# nm_npu_proc.net
KiCad netlist of a schematic drawn in Altium Designer
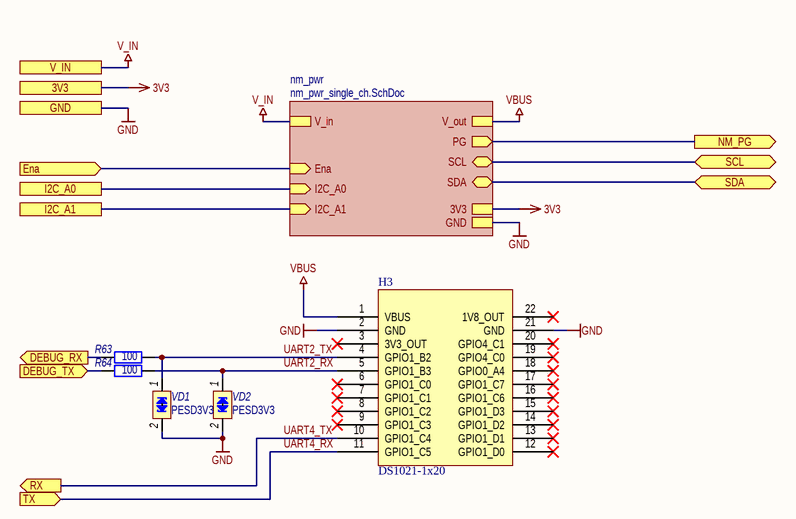
[diagram p0: nm_npu_proc.SchDoc]

(export (version "E")
  (design (tool "Eeschema 10.0.6"))
  (components
    (comp (ref "H3")
      (value "DS1021-1x20")
      (footprint "DS1021-1x20")
      (libsource (lib "DS1021-1x20") (part "DS1021-1x20"))
    )
    (comp (ref "R63")
      (value "100")
      (footprint "SMD_0603")
      (description "Resistor")
      (libsource (lib "Passive") (part "Resistor"))
    )
    (comp (ref "R64")
      (value "100")
      (footprint "SMD_0603")
      (description "Resistor")
      (libsource (lib "Passive") (part "Resistor"))
    )
    (comp (ref "VD1")
      (value "PESD3V3")
      (footprint "SOD-323")
      (description "Low capacitance bidirectional ESD protection diodes")
      (libsource (lib "Diod") (part "PESDxL1BA"))
    )
    (comp (ref "VD2")
      (value "PESD3V3")
      (footprint "SOD-323")
      (description "Low capacitance bidirectional ESD protection diodes")
      (libsource (lib "Diod") (part "PESDxL1BA"))
    )
  )
  (nets
    (net (code "1") (name "/DEBUG_RX") (class "Default")
      (node (ref "R63") (pin "1") (pinfunction "1_1") (pintype "passive"))
    )
    (net (code "2") (name "/DEBUG_TX") (class "Default")
      (node (ref "R64") (pin "1") (pinfunction "1_1") (pintype "passive"))
    )
    (net (code "9") (name "/UART2_RX") (class "Default")
      (node (ref "H3") (pin "5") (pinfunction "GPIO1_B3_5") (pintype "passive"))
      (node (ref "R64") (pin "2") (pinfunction "2_2") (pintype "passive"))
      (node (ref "VD2") (pin "1") (pinfunction "cathode_1_1") (pintype "passive"))
    )
    (net (code "10") (name "/UART2_TX") (class "Default")
      (node (ref "H3") (pin "4") (pinfunction "GPIO1_B2_4") (pintype "passive"))
      (node (ref "R63") (pin "2") (pinfunction "2_2") (pintype "passive"))
      (node (ref "VD1") (pin "1") (pinfunction "cathode_1_1") (pintype "passive"))
    )
    (net (code "11") (name "/UART4_RX") (class "Default")
      (node (ref "H3") (pin "11") (pinfunction "GPIO1_C5_11") (pintype "passive"))
    )
    (net (code "12") (name "/UART4_TX") (class "Default")
      (node (ref "H3") (pin "10") (pinfunction "GPIO1_C4_10") (pintype "passive"))
    )
    (net (code "14") (name "GND") (class "Default")
      (node (ref "H3") (pin "2") (pinfunction "GND_2") (pintype "power_in"))
      (node (ref "H3") (pin "21") (pinfunction "GND_21") (pintype "power_in"))
      (node (ref "VD1") (pin "2") (pinfunction "cathode_2_2") (pintype "passive"))
      (node (ref "VD2") (pin "2") (pinfunction "cathode_2_2") (pintype "passive"))
    )
    (net (code "15") (name "VBUS") (class "Default")
      (node (ref "H3") (pin "1") (pinfunction "VBUS_1") (pintype "power_in"))
    )
    (net (code "17") (name "unconnected-(H3-1V8_OUT-Pad22)") (class "Default")
      (node (ref "H3") (pin "22") (pinfunction "1V8_OUT_22") (pintype "power_in+no_connect"))
    )
    (net (code "18") (name "unconnected-(H3-3V3_OUT-Pad3)") (class "Default")
      (node (ref "H3") (pin "3") (pinfunction "3V3_OUT_3") (pintype "power_in+no_connect"))
    )
    (net (code "19") (name "unconnected-(H3-GPIO0_A4-Pad18)") (class "Default")
      (node (ref "H3") (pin "18") (pinfunction "GPIO0_A4_18") (pintype "passive+no_connect"))
    )
    (net (code "20") (name "unconnected-(H3-GPIO1_C0-Pad6)") (class "Default")
      (node (ref "H3") (pin "6") (pinfunction "GPIO1_C0_6") (pintype "passive+no_connect"))
    )
    (net (code "21") (name "unconnected-(H3-GPIO1_C1-Pad7)") (class "Default")
      (node (ref "H3") (pin "7") (pinfunction "GPIO1_C1_7") (pintype "passive+no_connect"))
    )
    (net (code "22") (name "unconnected-(H3-GPIO1_C2-Pad8)") (class "Default")
      (node (ref "H3") (pin "8") (pinfunction "GPIO1_C2_8") (pintype "passive+no_connect"))
    )
    (net (code "23") (name "unconnected-(H3-GPIO1_C3-Pad9)") (class "Default")
      (node (ref "H3") (pin "9") (pinfunction "GPIO1_C3_9") (pintype "passive+no_connect"))
    )
    (net (code "24") (name "unconnected-(H3-GPIO1_C6-Pad16)") (class "Default")
      (node (ref "H3") (pin "16") (pinfunction "GPIO1_C6_16") (pintype "passive+no_connect"))
    )
    (net (code "25") (name "unconnected-(H3-GPIO1_C7-Pad17)") (class "Default")
      (node (ref "H3") (pin "17") (pinfunction "GPIO1_C7_17") (pintype "passive+no_connect"))
    )
    (net (code "26") (name "unconnected-(H3-GPIO1_D0-Pad12)") (class "Default")
      (node (ref "H3") (pin "12") (pinfunction "GPIO1_D0_12") (pintype "passive+no_connect"))
    )
    (net (code "27") (name "unconnected-(H3-GPIO1_D1-Pad13)") (class "Default")
      (node (ref "H3") (pin "13") (pinfunction "GPIO1_D1_13") (pintype "passive+no_connect"))
    )
    (net (code "28") (name "unconnected-(H3-GPIO1_D2-Pad14)") (class "Default")
      (node (ref "H3") (pin "14") (pinfunction "GPIO1_D2_14") (pintype "passive+no_connect"))
    )
    (net (code "29") (name "unconnected-(H3-GPIO1_D3-Pad15)") (class "Default")
      (node (ref "H3") (pin "15") (pinfunction "GPIO1_D3_15") (pintype "passive+no_connect"))
    )
    (net (code "30") (name "unconnected-(H3-GPIO4_C0-Pad19)") (class "Default")
      (node (ref "H3") (pin "19") (pinfunction "GPIO4_C0_19") (pintype "passive+no_connect"))
    )
    (net (code "31") (name "unconnected-(H3-GPIO4_C1-Pad20)") (class "Default")
      (node (ref "H3") (pin "20") (pinfunction "GPIO4_C1_20") (pintype "passive+no_connect"))
    )
  )
)
